# untitled.net
KiCad netlist of a schematic drawn in EAGLE
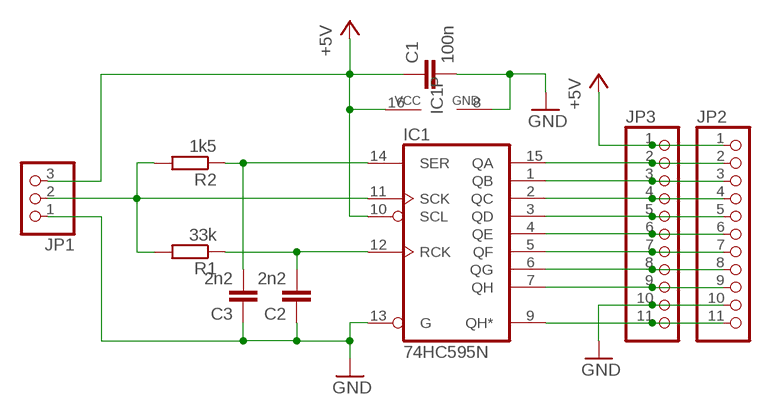
[diagram p0: schematic, sheet 1]

(export (version "E")
  (design (tool "Eeschema 10.0.6"))
  (components
    (comp (ref "C1")
      (value "100n")
      (footprint "eagle-import:C025-025X050")
      (libsource (lib "eagle-import") (part "C-EU025-025X050"))
    )
    (comp (ref "C2")
      (value "2n2")
      (footprint "eagle-import:C025-025X050")
      (libsource (lib "eagle-import") (part "C-EU025-025X050"))
    )
    (comp (ref "C3")
      (value "2n2")
      (footprint "eagle-import:C025-025X050")
      (libsource (lib "eagle-import") (part "C-EU025-025X050"))
    )
    (comp (ref "IC1")
      (value "74HC595N")
      (footprint "eagle-import:DIL16")
      (libsource (lib "eagle-import") (part "74595NHC"))
    )
    (comp (ref "JP1")
      (value "PINHD-1X3")
      (footprint "eagle-import:1X03")
      (libsource (lib "eagle-import") (part "PINHD-1X3"))
    )
    (comp (ref "JP2")
      (value "PINHD-1X11")
      (footprint "eagle-import:1X11")
      (libsource (lib "eagle-import") (part "PINHD-1X11"))
    )
    (comp (ref "JP3")
      (value "PINHD-1X11")
      (footprint "eagle-import:1X11")
      (libsource (lib "eagle-import") (part "PINHD-1X11"))
    )
    (comp (ref "R1")
      (value "33k")
      (footprint "eagle-import:0204_7")
      (libsource (lib "eagle-import") (part "R-EU_0204/7"))
    )
    (comp (ref "R2")
      (value "1k5")
      (footprint "eagle-import:0204_7")
      (libsource (lib "eagle-import") (part "R-EU_0204/7"))
    )
  )
  (nets
    (net (code "1") (name "+5V") (class "Default")
      (node (ref "C1") (pin "1") (pinfunction "1_1") (pintype "passive"))
      (node (ref "IC1") (pin "10") (pinfunction "SCL_10") (pintype "input"))
      (node (ref "IC1") (pin "16") (pinfunction "VCC_16") (pintype "power_in"))
      (node (ref "JP1") (pin "3") (pinfunction "3_3") (pintype "passive"))
      (node (ref "JP2") (pin "1") (pinfunction "1_1") (pintype "passive"))
      (node (ref "JP3") (pin "1") (pinfunction "1_1") (pintype "passive"))
    )
    (net (code "2") (name "GND") (class "Default")
      (node (ref "C1") (pin "2") (pinfunction "2_2") (pintype "passive"))
      (node (ref "C2") (pin "1") (pinfunction "1_1") (pintype "passive"))
      (node (ref "C3") (pin "1") (pinfunction "1_1") (pintype "passive"))
      (node (ref "IC1") (pin "13") (pinfunction "G_13") (pintype "input"))
      (node (ref "IC1") (pin "8") (pinfunction "GND_8") (pintype "power_in"))
      (node (ref "JP1") (pin "1") (pinfunction "1_1") (pintype "passive"))
      (node (ref "JP2") (pin "10") (pinfunction "10_10") (pintype "passive"))
      (node (ref "JP3") (pin "10") (pinfunction "10_10") (pintype "passive"))
    )
    (net (code "3") (name "Net-(IC1A-QA)") (class "Default")
      (node (ref "IC1") (pin "15") (pinfunction "QA_15") (pintype "tri_state"))
      (node (ref "JP2") (pin "2") (pinfunction "2_2") (pintype "passive"))
      (node (ref "JP3") (pin "2") (pinfunction "2_2") (pintype "passive"))
    )
    (net (code "4") (name "Net-(IC1A-QB)") (class "Default")
      (node (ref "IC1") (pin "1") (pinfunction "QB_1") (pintype "tri_state"))
      (node (ref "JP2") (pin "3") (pinfunction "3_3") (pintype "passive"))
      (node (ref "JP3") (pin "3") (pinfunction "3_3") (pintype "passive"))
    )
    (net (code "5") (name "Net-(IC1A-QC)") (class "Default")
      (node (ref "IC1") (pin "2") (pinfunction "QC_2") (pintype "tri_state"))
      (node (ref "JP2") (pin "4") (pinfunction "4_4") (pintype "passive"))
      (node (ref "JP3") (pin "4") (pinfunction "4_4") (pintype "passive"))
    )
    (net (code "6") (name "Net-(IC1A-QD)") (class "Default")
      (node (ref "IC1") (pin "3") (pinfunction "QD_3") (pintype "tri_state"))
      (node (ref "JP2") (pin "5") (pinfunction "5_5") (pintype "passive"))
      (node (ref "JP3") (pin "5") (pinfunction "5_5") (pintype "passive"))
    )
    (net (code "7") (name "Net-(IC1A-QE)") (class "Default")
      (node (ref "IC1") (pin "4") (pinfunction "QE_4") (pintype "tri_state"))
      (node (ref "JP2") (pin "6") (pinfunction "6_6") (pintype "passive"))
      (node (ref "JP3") (pin "6") (pinfunction "6_6") (pintype "passive"))
    )
    (net (code "8") (name "Net-(IC1A-QF)") (class "Default")
      (node (ref "IC1") (pin "5") (pinfunction "QF_5") (pintype "tri_state"))
      (node (ref "JP2") (pin "7") (pinfunction "7_7") (pintype "passive"))
      (node (ref "JP3") (pin "7") (pinfunction "7_7") (pintype "passive"))
    )
    (net (code "9") (name "Net-(IC1A-QG)") (class "Default")
      (node (ref "IC1") (pin "6") (pinfunction "QG_6") (pintype "tri_state"))
      (node (ref "JP2") (pin "8") (pinfunction "8_8") (pintype "passive"))
      (node (ref "JP3") (pin "8") (pinfunction "8_8") (pintype "passive"))
    )
    (net (code "10") (name "Net-(IC1A-QH)") (class "Default")
      (node (ref "IC1") (pin "7") (pinfunction "QH_7") (pintype "tri_state"))
      (node (ref "JP2") (pin "9") (pinfunction "9_9") (pintype "passive"))
      (node (ref "JP3") (pin "9") (pinfunction "9_9") (pintype "passive"))
    )
    (net (code "11") (name "Net-(IC1A-QH*)") (class "Default")
      (node (ref "IC1") (pin "9") (pinfunction "QH*_9") (pintype "tri_state"))
      (node (ref "JP2") (pin "11") (pinfunction "11_11") (pintype "passive"))
      (node (ref "JP3") (pin "11") (pinfunction "11_11") (pintype "passive"))
    )
    (net (code "12") (name "Net-(IC1A-RCK)") (class "Default")
      (node (ref "C2") (pin "2") (pinfunction "2_2") (pintype "passive"))
      (node (ref "IC1") (pin "12") (pinfunction "RCK_12") (pintype "input"))
      (node (ref "R1") (pin "1") (pinfunction "1_1") (pintype "passive"))
    )
    (net (code "13") (name "Net-(IC1A-SCK)") (class "Default")
      (node (ref "IC1") (pin "11") (pinfunction "SCK_11") (pintype "input"))
      (node (ref "JP1") (pin "2") (pinfunction "2_2") (pintype "passive"))
      (node (ref "R1") (pin "2") (pinfunction "2_2") (pintype "passive"))
      (node (ref "R2") (pin "2") (pinfunction "2_2") (pintype "passive"))
    )
    (net (code "14") (name "Net-(IC1A-SER)") (class "Default")
      (node (ref "C3") (pin "2") (pinfunction "2_2") (pintype "passive"))
      (node (ref "IC1") (pin "14") (pinfunction "SER_14") (pintype "input"))
      (node (ref "R2") (pin "1") (pinfunction "1_1") (pintype "passive"))
    )
  )
)
